# 1-Schematic_8052Explorer_PLCC.net
KiCad netlist of a schematic drawn in EasyEDA
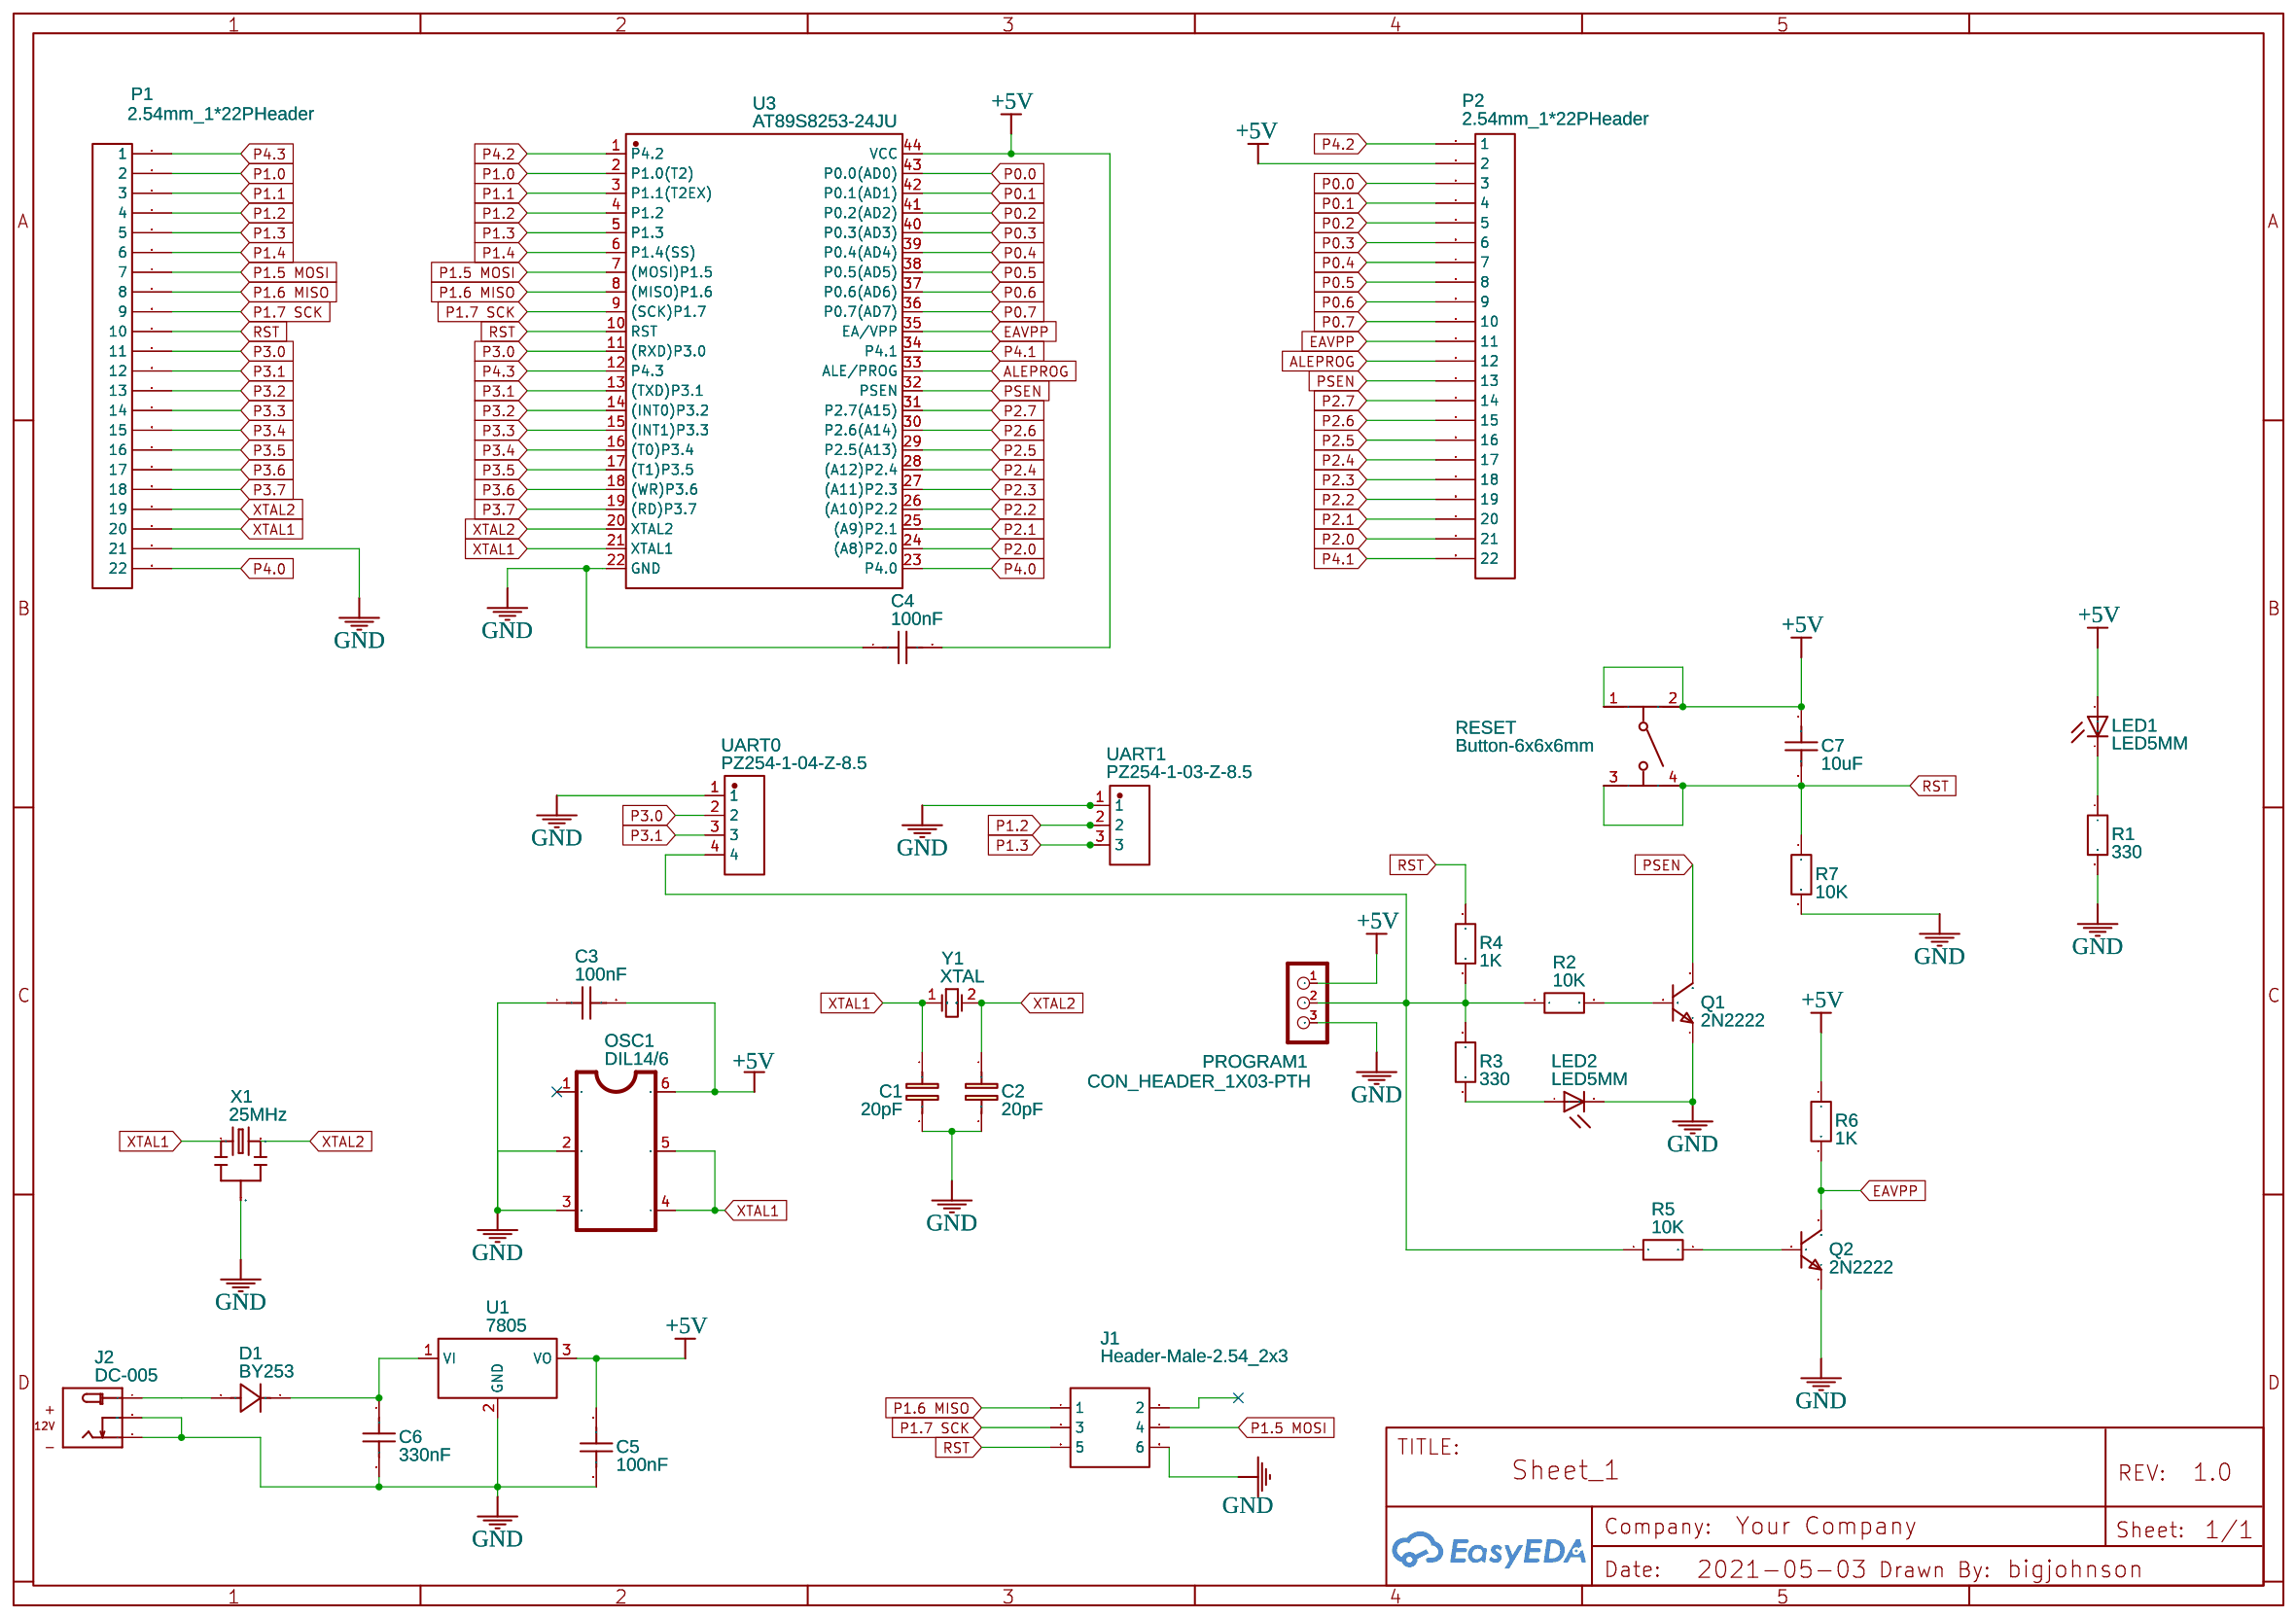
[diagram p0: schematic sheet]

(export (version "E")
  (design (tool "Eeschema 10.0.6"))
  (components
    (comp (ref "C1")
      (value "20pF")
      (fields (field (name "BOM_Supplier Part") "9000274010"))
      (libsource (lib "") (part "20pF copy"))
    )
    (comp (ref "C2")
      (value "20pF")
      (fields (field (name "BOM_Supplier Part") "9000274010"))
      (libsource (lib "") (part "20pF copy"))
    )
    (comp (ref "C3")
      (value "100nF")
      (fields
        (field (name "BOM_Manufacturer Part") "CT4-0805B103 K500")
        (field (name "BOM_Supplier Part") "C8033")
      )
      (libsource (lib "") (part "CT4-0805B103 K500_1"))
    )
    (comp (ref "C4")
      (value "100nF")
      (fields
        (field (name "BOM_Manufacturer Part") "CT4-0805B103 K500")
        (field (name "BOM_Supplier Part") "C8033")
      )
      (libsource (lib "") (part "CT4-0805B103 K500_1"))
    )
    (comp (ref "C5")
      (value "100nF")
      (fields
        (field (name "BOM_Manufacturer Part") "CT4-0805B103 K500")
        (field (name "BOM_Supplier Part") "C8033")
      )
      (libsource (lib "") (part "CT4-0805B103 K500"))
    )
    (comp (ref "C6")
      (value "330nF")
      (fields
        (field (name "BOM_Manufacturer Part") "CT4-0805B103 K500")
        (field (name "BOM_Supplier Part") "C8033")
      )
      (libsource (lib "") (part "CT4-0805B103 K500"))
    )
    (comp (ref "C7")
      (value "10uF")
      (fields
        (field (name "BOM_Manufacturer Part") "CT4-0805B103 K500")
        (field (name "BOM_Supplier Part") "C8033")
      )
      (libsource (lib "") (part "CT4-0805B103 K500"))
    )
    (comp (ref "D1")
      (value "BY253")
      (fields (field (name "BOM_Manufacturer Part") "MUR460") (field (name "BOM_Supplier Part") "C2990844"))
      (libsource (lib "") (part "MUR460_C2990844"))
    )
    (comp (ref "J1")
      (value "Header-Male-2.54_2x3")
      (fields (field (name "BOM_Supplier Part") "C65114"))
      (libsource (lib "") (part "Header-Male-2.54_2x3"))
    )
    (comp (ref "J2") (value "DC-005") (libsource (lib "") (part "DC-005")))
    (comp (ref "LED1") (value "LED5MM") (libsource (lib "") (part "LED5MM_1")))
    (comp (ref "LED2") (value "LED5MM") (libsource (lib "") (part "LED5MM")))
    (comp (ref "OSC1") (value "DIL14/6") (libsource (lib "") (part "DIL14/3")))
    (comp (ref "P1")
      (value "2.54mm_1*22PHeader")
      (fields
        (field (name "BOM_Manufacturer Part") "2.54mm 1*22PHeader")
        (field (name "BOM_Supplier Part") "C50981")
      )
      (libsource (lib "") (part "2.54mm_1*22PHeader"))
    )
    (comp (ref "P2")
      (value "2.54mm_1*22PHeader")
      (fields
        (field (name "BOM_Manufacturer Part") "2.54mm 1*22PHeader")
        (field (name "BOM_Supplier Part") "C50981")
      )
      (libsource (lib "") (part "2.54mm_1*22PHeader_1"))
    )
    (comp (ref "PROGRAM1") (value "CON_HEADER_1X03-PTH") (libsource (lib "") (part "CON_HEADER_1X03-PTH")))
    (comp (ref "Q1")
      (value "2N2222")
      (fields (field (name "BOM_Supplier Part") "C118536"))
      (libsource (lib "") (part "2N2222"))
    )
    (comp (ref "Q2")
      (value "2N2222")
      (fields (field (name "BOM_Supplier Part") "C118536"))
      (libsource (lib "") (part "2N2222"))
    )
    (comp (ref "R1") (value "330") (libsource (lib "") (part "Res_AXIAL-0.4(1/4W)_EU")))
    (comp (ref "R2") (value "10K") (libsource (lib "") (part "Res_AXIAL-0.4(1/4W)_EU_1")))
    (comp (ref "R3") (value "330") (libsource (lib "") (part "Res_AXIAL-0.4(1/4W)_EU")))
    (comp (ref "R4") (value "1K") (libsource (lib "") (part "Res_AXIAL-0.4(1/4W)_EU")))
    (comp (ref "R5") (value "10K") (libsource (lib "") (part "Res_AXIAL-0.4(1/4W)_EU_1")))
    (comp (ref "R6") (value "1K") (libsource (lib "") (part "Res_AXIAL-0.4(1/4W)_EU")))
    (comp (ref "R7") (value "10K") (libsource (lib "") (part "Res_AXIAL-0.4(1/4W)_EU")))
    (comp (ref "RESET")
      (value "Button-6x6x6mm")
      (fields
        (field (name "BOM_Manufacturer Part") "Switch,6*6*6Plastic head,260G, 0.25mm,Straight line")
        (field (name "BOM_Supplier Part") "C71836")
      )
      (libsource (lib "") (part "Button-6x6x6mm"))
    )
    (comp (ref "U1")
      (value "7805")
      (fields (field (name "BOM_Supplier Part") "C305416"))
      (libsource (lib "") (part "7805"))
    )
    (comp (ref "U3")
      (value "AT89S8253-24JU")
      (fields (field (name "BOM_Supplier Part") "C614054"))
      (libsource (lib "") (part "AT89S8253-24JU"))
    )
    (comp (ref "UART0")
      (value "PZ254-1-04-Z-8.5")
      (fields (field (name "BOM_Supplier Part") "C2894927"))
      (libsource (lib "") (part "PZ254-1-04-Z-8.5"))
    )
    (comp (ref "UART1")
      (value "PZ254-1-03-Z-8.5")
      (fields (field (name "BOM_Supplier Part") "C2894926"))
      (libsource (lib "") (part "PZ254-1-03-Z-8.5"))
    )
    (comp (ref "X1")
      (value "25MHz")
      (fields
        (field (name "BOM_Manufacturer Part") "Resonator 433.92MHZ")
        (field (name "BOM_Supplier Part") "C71016")
      )
      (libsource (lib "") (part "Ceramic Resonator 16 MHz"))
    )
    (comp (ref "Y1") (value "XTAL") (libsource (lib "") (part "XTAL")))
  )
  (nets
    (net (code "1") (name "+5V") (class "Default")
      (node (ref "C3") (pin "2") (pinfunction "2_2") (pintype "unspecified"))
      (node (ref "C4") (pin "2") (pinfunction "2_2") (pintype "unspecified"))
      (node (ref "C5") (pin "1") (pinfunction "1_1") (pintype "unspecified"))
      (node (ref "C7") (pin "1") (pinfunction "1_1") (pintype "unspecified"))
      (node (ref "LED1") (pin "A") (pinfunction "A_A") (pintype "unspecified"))
      (node (ref "OSC1") (pin "6") (pinfunction "6_6") (pintype "unspecified"))
      (node (ref "P2") (pin "2") (pinfunction "2_2") (pintype "input"))
      (node (ref "PROGRAM1") (pin "1") (pinfunction "1_1") (pintype "unspecified"))
      (node (ref "R6") (pin "1") (pinfunction "1_1") (pintype "unspecified"))
      (node (ref "RESET") (pin "1") (pinfunction "1_1") (pintype "unspecified"))
      (node (ref "RESET") (pin "2") (pinfunction "2_2") (pintype "unspecified"))
      (node (ref "U1") (pin "3") (pinfunction "VO_3") (pintype "unspecified"))
      (node (ref "U3") (pin "44") (pinfunction "VCC_44") (pintype "unspecified"))
    )
    (net (code "2") (name "ALEPROG") (class "Default")
      (node (ref "P2") (pin "12") (pinfunction "12_12") (pintype "input"))
      (node (ref "U3") (pin "33") (pinfunction "ALE/PROG_33") (pintype "unspecified"))
    )
    (net (code "3") (name "EAVPP") (class "Default")
      (node (ref "P2") (pin "11") (pinfunction "11_11") (pintype "input"))
      (node (ref "Q2") (pin "3") (pinfunction "C_3") (pintype "unspecified"))
      (node (ref "R6") (pin "2") (pinfunction "2_2") (pintype "unspecified"))
      (node (ref "U3") (pin "35") (pinfunction "EA/VPP_35") (pintype "unspecified"))
    )
    (net (code "4") (name "GND") (class "Default")
      (node (ref "C1") (pin "2") (pinfunction "1_2") (pintype "unspecified"))
      (node (ref "C2") (pin "2") (pinfunction "1_2") (pintype "unspecified"))
      (node (ref "C3") (pin "1") (pinfunction "1_1") (pintype "unspecified"))
      (node (ref "C4") (pin "1") (pinfunction "1_1") (pintype "unspecified"))
      (node (ref "C5") (pin "2") (pinfunction "2_2") (pintype "unspecified"))
      (node (ref "C6") (pin "2") (pinfunction "2_2") (pintype "unspecified"))
      (node (ref "J1") (pin "6") (pinfunction "6_6") (pintype "input"))
      (node (ref "J2") (pin "-1") (pinfunction "-_-1") (pintype "unspecified"))
      (node (ref "J2") (pin "-2") (pinfunction "CDN_-2") (pintype "unspecified"))
      (node (ref "LED2") (pin "K") (pinfunction "C_K") (pintype "unspecified"))
      (node (ref "OSC1") (pin "2") (pinfunction "2_2") (pintype "unspecified"))
      (node (ref "OSC1") (pin "3") (pinfunction "3_3") (pintype "unspecified"))
      (node (ref "P1") (pin "21") (pinfunction "21_21") (pintype "unspecified"))
      (node (ref "PROGRAM1") (pin "3") (pinfunction "3_3") (pintype "unspecified"))
      (node (ref "Q1") (pin "1") (pinfunction "E_1") (pintype "unspecified"))
      (node (ref "Q2") (pin "1") (pinfunction "E_1") (pintype "unspecified"))
      (node (ref "R1") (pin "2") (pinfunction "2_2") (pintype "unspecified"))
      (node (ref "R7") (pin "2") (pinfunction "2_2") (pintype "unspecified"))
      (node (ref "U1") (pin "2") (pinfunction "GND_2") (pintype "unspecified"))
      (node (ref "U3") (pin "22") (pinfunction "GND_22") (pintype "unspecified"))
      (node (ref "UART0") (pin "1") (pinfunction "1_1") (pintype "unspecified"))
      (node (ref "UART1") (pin "1") (pinfunction "1_1") (pintype "unspecified"))
      (node (ref "X1") (pin "2") (pinfunction "2_2") (pintype "unspecified"))
    )
    (net (code "5") (name "Net-(D1-A)") (class "Default")
      (node (ref "D1") (pin "2") (pinfunction "A_2") (pintype "unspecified"))
      (node (ref "J2") (pin "+") (pinfunction "+_+") (pintype "unspecified"))
    )
    (net (code "6") (name "Net-(D1-K)") (class "Default")
      (node (ref "C6") (pin "1") (pinfunction "1_1") (pintype "unspecified"))
      (node (ref "D1") (pin "1") (pinfunction "K_1") (pintype "unspecified"))
      (node (ref "U1") (pin "1") (pinfunction "VI_1") (pintype "unspecified"))
    )
    (net (code "7") (name "Net-(LED1-C)") (class "Default")
      (node (ref "LED1") (pin "K") (pinfunction "C_K") (pintype "unspecified"))
      (node (ref "R1") (pin "1") (pinfunction "1_1") (pintype "unspecified"))
    )
    (net (code "8") (name "Net-(LED2-PadA)") (class "Default")
      (node (ref "LED2") (pin "A") (pinfunction "A_A") (pintype "unspecified"))
      (node (ref "R3") (pin "2") (pinfunction "2_2") (pintype "unspecified"))
    )
    (net (code "9") (name "Net-(PROGRAM1-Pad2)") (class "Default")
      (node (ref "PROGRAM1") (pin "2") (pinfunction "2_2") (pintype "unspecified"))
      (node (ref "R2") (pin "1") (pinfunction "1_1") (pintype "unspecified"))
      (node (ref "R3") (pin "1") (pinfunction "1_1") (pintype "unspecified"))
      (node (ref "R4") (pin "2") (pinfunction "2_2") (pintype "unspecified"))
      (node (ref "R5") (pin "1") (pinfunction "1_1") (pintype "unspecified"))
      (node (ref "UART0") (pin "4") (pinfunction "4_4") (pintype "unspecified"))
    )
    (net (code "10") (name "Net-(Q1-B)") (class "Default")
      (node (ref "Q1") (pin "2") (pinfunction "B_2") (pintype "unspecified"))
      (node (ref "R2") (pin "2") (pinfunction "2_2") (pintype "unspecified"))
    )
    (net (code "11") (name "Net-(Q2-B)") (class "Default")
      (node (ref "Q2") (pin "2") (pinfunction "B_2") (pintype "unspecified"))
      (node (ref "R5") (pin "2") (pinfunction "2_2") (pintype "unspecified"))
    )
    (net (code "12") (name "P0.0") (class "Default")
      (node (ref "P2") (pin "3") (pinfunction "3_3") (pintype "input"))
      (node (ref "U3") (pin "43") (pinfunction "P0.0(AD0)_43") (pintype "unspecified"))
    )
    (net (code "13") (name "P0.1") (class "Default")
      (node (ref "P2") (pin "4") (pinfunction "4_4") (pintype "input"))
      (node (ref "U3") (pin "42") (pinfunction "P0.1(AD1)_42") (pintype "unspecified"))
    )
    (net (code "14") (name "P0.2") (class "Default")
      (node (ref "P2") (pin "5") (pinfunction "5_5") (pintype "input"))
      (node (ref "U3") (pin "41") (pinfunction "P0.2(AD2)_41") (pintype "unspecified"))
    )
    (net (code "15") (name "P0.3") (class "Default")
      (node (ref "P2") (pin "6") (pinfunction "6_6") (pintype "input"))
      (node (ref "U3") (pin "40") (pinfunction "P0.3(AD3)_40") (pintype "unspecified"))
    )
    (net (code "16") (name "P0.4") (class "Default")
      (node (ref "P2") (pin "7") (pinfunction "7_7") (pintype "input"))
      (node (ref "U3") (pin "39") (pinfunction "P0.4(AD4)_39") (pintype "unspecified"))
    )
    (net (code "17") (name "P0.5") (class "Default")
      (node (ref "P2") (pin "8") (pinfunction "8_8") (pintype "input"))
      (node (ref "U3") (pin "38") (pinfunction "P0.5(AD5)_38") (pintype "unspecified"))
    )
    (net (code "18") (name "P0.6") (class "Default")
      (node (ref "P2") (pin "9") (pinfunction "9_9") (pintype "input"))
      (node (ref "U3") (pin "37") (pinfunction "P0.6(AD6)_37") (pintype "unspecified"))
    )
    (net (code "19") (name "P0.7") (class "Default")
      (node (ref "P2") (pin "10") (pinfunction "10_10") (pintype "input"))
      (node (ref "U3") (pin "36") (pinfunction "P0.7(AD7)_36") (pintype "unspecified"))
    )
    (net (code "20") (name "P1.0") (class "Default")
      (node (ref "P1") (pin "2") (pinfunction "2_2") (pintype "input"))
      (node (ref "U3") (pin "2") (pinfunction "P1.0(T2)_2") (pintype "unspecified"))
    )
    (net (code "21") (name "P1.1") (class "Default")
      (node (ref "P1") (pin "3") (pinfunction "3_3") (pintype "input"))
      (node (ref "U3") (pin "3") (pinfunction "P1.1(T2EX)_3") (pintype "unspecified"))
    )
    (net (code "22") (name "P1.2") (class "Default")
      (node (ref "P1") (pin "4") (pinfunction "4_4") (pintype "input"))
      (node (ref "U3") (pin "4") (pinfunction "P1.2_4") (pintype "unspecified"))
      (node (ref "UART1") (pin "2") (pinfunction "2_2") (pintype "unspecified"))
    )
    (net (code "23") (name "P1.3") (class "Default")
      (node (ref "P1") (pin "5") (pinfunction "5_5") (pintype "input"))
      (node (ref "U3") (pin "5") (pinfunction "P1.3_5") (pintype "unspecified"))
      (node (ref "UART1") (pin "3") (pinfunction "3_3") (pintype "unspecified"))
    )
    (net (code "24") (name "P1.4") (class "Default")
      (node (ref "P1") (pin "6") (pinfunction "6_6") (pintype "input"))
      (node (ref "U3") (pin "6") (pinfunction "P1.4(SS)_6") (pintype "unspecified"))
    )
    (net (code "25") (name "P1.5 MOSI") (class "Default")
      (node (ref "J1") (pin "4") (pinfunction "4_4") (pintype "input"))
      (node (ref "P1") (pin "7") (pinfunction "7_7") (pintype "input"))
      (node (ref "U3") (pin "7") (pinfunction "(MOSI)P1.5_7") (pintype "unspecified"))
    )
    (net (code "26") (name "P1.6 MISO") (class "Default")
      (node (ref "J1") (pin "1") (pinfunction "1_1") (pintype "input"))
      (node (ref "P1") (pin "8") (pinfunction "8_8") (pintype "input"))
      (node (ref "U3") (pin "8") (pinfunction "(MISO)P1.6_8") (pintype "unspecified"))
    )
    (net (code "27") (name "P1.7 SCK") (class "Default")
      (node (ref "J1") (pin "3") (pinfunction "3_3") (pintype "input"))
      (node (ref "P1") (pin "9") (pinfunction "9_9") (pintype "input"))
      (node (ref "U3") (pin "9") (pinfunction "(SCK)P1.7_9") (pintype "unspecified"))
    )
    (net (code "28") (name "P2.0") (class "Default")
      (node (ref "P2") (pin "21") (pinfunction "21_21") (pintype "unspecified"))
      (node (ref "U3") (pin "24") (pinfunction "(A8)P2.0_24") (pintype "unspecified"))
    )
    (net (code "29") (name "P2.1") (class "Default")
      (node (ref "P2") (pin "20") (pinfunction "20_20") (pintype "input"))
      (node (ref "U3") (pin "25") (pinfunction "(A9)P2.1_25") (pintype "unspecified"))
    )
    (net (code "30") (name "P2.2") (class "Default")
      (node (ref "P2") (pin "19") (pinfunction "19_19") (pintype "input"))
      (node (ref "U3") (pin "26") (pinfunction "(A10)P2.2_26") (pintype "unspecified"))
    )
    (net (code "31") (name "P2.3") (class "Default")
      (node (ref "P2") (pin "18") (pinfunction "18_18") (pintype "input"))
      (node (ref "U3") (pin "27") (pinfunction "(A11)P2.3_27") (pintype "unspecified"))
    )
    (net (code "32") (name "P2.4") (class "Default")
      (node (ref "P2") (pin "17") (pinfunction "17_17") (pintype "input"))
      (node (ref "U3") (pin "28") (pinfunction "(A12)P2.4_28") (pintype "unspecified"))
    )
    (net (code "33") (name "P2.5") (class "Default")
      (node (ref "P2") (pin "16") (pinfunction "16_16") (pintype "input"))
      (node (ref "U3") (pin "29") (pinfunction "P2.5(A13)_29") (pintype "unspecified"))
    )
    (net (code "34") (name "P2.6") (class "Default")
      (node (ref "P2") (pin "15") (pinfunction "15_15") (pintype "input"))
      (node (ref "U3") (pin "30") (pinfunction "P2.6(A14)_30") (pintype "unspecified"))
    )
    (net (code "35") (name "P2.7") (class "Default")
      (node (ref "P2") (pin "14") (pinfunction "14_14") (pintype "input"))
      (node (ref "U3") (pin "31") (pinfunction "P2.7(A15)_31") (pintype "unspecified"))
    )
    (net (code "36") (name "P3.0") (class "Default")
      (node (ref "P1") (pin "11") (pinfunction "11_11") (pintype "input"))
      (node (ref "U3") (pin "11") (pinfunction "(RXD)P3.0_11") (pintype "unspecified"))
      (node (ref "UART0") (pin "2") (pinfunction "2_2") (pintype "unspecified"))
    )
    (net (code "37") (name "P3.1") (class "Default")
      (node (ref "P1") (pin "12") (pinfunction "12_12") (pintype "input"))
      (node (ref "U3") (pin "13") (pinfunction "(TXD)P3.1_13") (pintype "unspecified"))
      (node (ref "UART0") (pin "3") (pinfunction "3_3") (pintype "unspecified"))
    )
    (net (code "38") (name "P3.2") (class "Default")
      (node (ref "P1") (pin "13") (pinfunction "13_13") (pintype "input"))
      (node (ref "U3") (pin "14") (pinfunction "(INT0)P3.2_14") (pintype "unspecified"))
    )
    (net (code "39") (name "P3.3") (class "Default")
      (node (ref "P1") (pin "14") (pinfunction "14_14") (pintype "input"))
      (node (ref "U3") (pin "15") (pinfunction "(INT1)P3.3_15") (pintype "unspecified"))
    )
    (net (code "40") (name "P3.4") (class "Default")
      (node (ref "P1") (pin "15") (pinfunction "15_15") (pintype "input"))
      (node (ref "U3") (pin "16") (pinfunction "(T0)P3.4_16") (pintype "unspecified"))
    )
    (net (code "41") (name "P3.5") (class "Default")
      (node (ref "P1") (pin "16") (pinfunction "16_16") (pintype "input"))
      (node (ref "U3") (pin "17") (pinfunction "(T1)P3.5_17") (pintype "unspecified"))
    )
    (net (code "42") (name "P3.6") (class "Default")
      (node (ref "P1") (pin "17") (pinfunction "17_17") (pintype "input"))
      (node (ref "U3") (pin "18") (pinfunction "(WR)P3.6_18") (pintype "unspecified"))
    )
    (net (code "43") (name "P3.7") (class "Default")
      (node (ref "P1") (pin "18") (pinfunction "18_18") (pintype "input"))
      (node (ref "U3") (pin "19") (pinfunction "(RD)P3.7_19") (pintype "unspecified"))
    )
    (net (code "44") (name "P4.0") (class "Default")
      (node (ref "P1") (pin "22") (pinfunction "22_22") (pintype "unspecified"))
      (node (ref "U3") (pin "23") (pinfunction "P4.0_23") (pintype "unspecified"))
    )
    (net (code "45") (name "P4.1") (class "Default")
      (node (ref "P2") (pin "22") (pinfunction "22_22") (pintype "unspecified"))
      (node (ref "U3") (pin "34") (pinfunction "P4.1_34") (pintype "unspecified"))
    )
    (net (code "46") (name "P4.2") (class "Default")
      (node (ref "P2") (pin "1") (pinfunction "1_1") (pintype "input"))
      (node (ref "U3") (pin "1") (pinfunction "P4.2_1") (pintype "unspecified"))
    )
    (net (code "47") (name "P4.3") (class "Default")
      (node (ref "P1") (pin "1") (pinfunction "1_1") (pintype "input"))
      (node (ref "U3") (pin "12") (pinfunction "P4.3_12") (pintype "unspecified"))
    )
    (net (code "48") (name "PSEN") (class "Default")
      (node (ref "P2") (pin "13") (pinfunction "13_13") (pintype "input"))
      (node (ref "Q1") (pin "3") (pinfunction "C_3") (pintype "unspecified"))
      (node (ref "U3") (pin "32") (pinfunction "PSEN_32") (pintype "unspecified"))
    )
    (net (code "49") (name "RST") (class "Default")
      (node (ref "C7") (pin "2") (pinfunction "2_2") (pintype "unspecified"))
      (node (ref "J1") (pin "5") (pinfunction "5_5") (pintype "input"))
      (node (ref "P1") (pin "10") (pinfunction "10_10") (pintype "input"))
      (node (ref "R4") (pin "1") (pinfunction "1_1") (pintype "unspecified"))
      (node (ref "R7") (pin "1") (pinfunction "1_1") (pintype "unspecified"))
      (node (ref "RESET") (pin "3") (pinfunction "3_3") (pintype "unspecified"))
      (node (ref "RESET") (pin "4") (pinfunction "4_4") (pintype "unspecified"))
      (node (ref "U3") (pin "10") (pinfunction "RST_10") (pintype "unspecified"))
    )
    (net (code "50") (name "XTAL1") (class "Default")
      (node (ref "C1") (pin "1") (pinfunction "1_1") (pintype "unspecified"))
      (node (ref "OSC1") (pin "4") (pinfunction "4_4") (pintype "unspecified"))
      (node (ref "OSC1") (pin "5") (pinfunction "5_5") (pintype "unspecified"))
      (node (ref "P1") (pin "20") (pinfunction "20_20") (pintype "input"))
      (node (ref "U3") (pin "21") (pinfunction "XTAL1_21") (pintype "unspecified"))
      (node (ref "X1") (pin "1") (pinfunction "1_1") (pintype "unspecified"))
      (node (ref "Y1") (pin "1") (pinfunction "OSC1_1") (pintype "unspecified"))
    )
    (net (code "51") (name "XTAL2") (class "Default")
      (node (ref "C2") (pin "1") (pinfunction "1_1") (pintype "unspecified"))
      (node (ref "P1") (pin "19") (pinfunction "19_19") (pintype "input"))
      (node (ref "U3") (pin "20") (pinfunction "XTAL2_20") (pintype "unspecified"))
      (node (ref "X1") (pin "3") (pinfunction "3_3") (pintype "unspecified"))
      (node (ref "Y1") (pin "2") (pinfunction "OSC2_2") (pintype "unspecified"))
    )
    (net (code "52") (name "unconnected-(J1-Pad2)") (class "Default")
      (node (ref "J1") (pin "2") (pinfunction "2_2") (pintype "input+no_connect"))
    )
    (net (code "53") (name "unconnected-(OSC1-Pad1)") (class "Default")
      (node (ref "OSC1") (pin "1") (pinfunction "1_1") (pintype "unspecified+no_connect"))
    )
  )
)
